# module.net
KiCad netlist of a schematic drawn in EAGLE
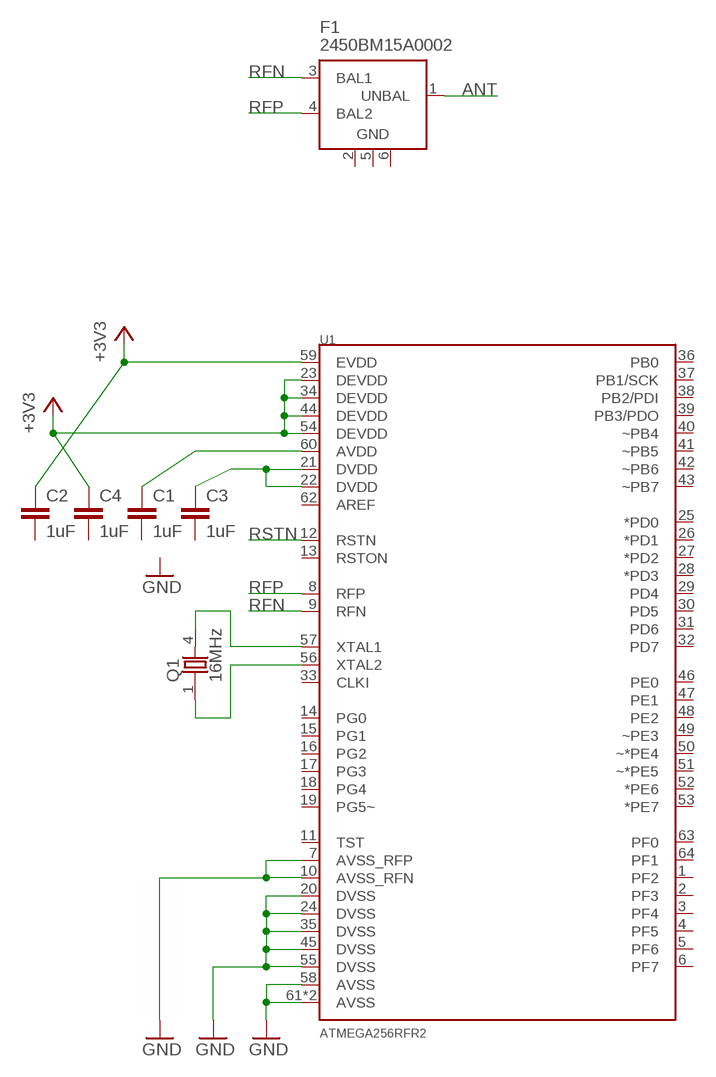
[diagram p0: schematic, sheet 1]

(export (version "E")
  (design (tool "Eeschema 10.0.6"))
  (components
    (comp (ref "C1")
      (value "1uF")
      (footprint "eagle-import:C0805K")
      (libsource (lib "eagle-import") (part "C-EUC0805K"))
    )
    (comp (ref "C2")
      (value "1uF")
      (footprint "eagle-import:C0805K")
      (libsource (lib "eagle-import") (part "C-EUC0805K"))
    )
    (comp (ref "C3")
      (value "1uF")
      (footprint "eagle-import:C0805K")
      (libsource (lib "eagle-import") (part "C-EUC0805K"))
    )
    (comp (ref "C4")
      (value "1uF")
      (footprint "eagle-import:C0805K")
      (libsource (lib "eagle-import") (part "C-EUC0805K"))
    )
    (comp (ref "F1")
      (value "2450BM15A0002")
      (footprint "eagle-import:2450BM15A0002")
      (libsource (lib "eagle-import") (part "2450BM15A0002"))
    )
    (comp (ref "Q1")
      (value "16MHz")
      (footprint "eagle-import:86SMX")
      (fields (field (name "MF") "C-MAC  FREQUENCY PRODUCTS LTD") (field (name "MPN") "XTAL003321- 86SMX"))
      (libsource (lib "eagle-import") (part "86SMX"))
    )
    (comp (ref "U1")
      (value "ATMEGA256RFR2")
      (footprint "eagle-import:QFN-64")
      (libsource (lib "eagle-import") (part "ATMEGA256RFR2"))
    )
  )
  (nets
    (net (code "1") (name "+3V3") (class "Default")
      (node (ref "C2") (pin "1") (pinfunction "1_1") (pintype "passive"))
      (node (ref "C4") (pin "1") (pinfunction "1_1") (pintype "passive"))
      (node (ref "U1") (pin "23") (pinfunction "DEVDD_23") (pintype "bidirectional"))
      (node (ref "U1") (pin "34") (pinfunction "DEVDD_34") (pintype "bidirectional"))
      (node (ref "U1") (pin "44") (pinfunction "DEVDD_44") (pintype "bidirectional"))
      (node (ref "U1") (pin "54") (pinfunction "DEVDD_54") (pintype "bidirectional"))
      (node (ref "U1") (pin "59") (pinfunction "EVDD_59") (pintype "bidirectional"))
    )
    (net (code "2") (name "/ANT") (class "Default")
      (node (ref "F1") (pin "1") (pinfunction "UNBAL_1") (pintype "passive"))
    )
    (net (code "3") (name "/RFN") (class "Default")
      (node (ref "F1") (pin "3") (pinfunction "BAL1_3") (pintype "passive"))
      (node (ref "U1") (pin "9") (pinfunction "RFN_9") (pintype "bidirectional"))
    )
    (net (code "4") (name "/RFP") (class "Default")
      (node (ref "F1") (pin "4") (pinfunction "BAL2_4") (pintype "passive"))
      (node (ref "U1") (pin "8") (pinfunction "RFP_8") (pintype "bidirectional"))
    )
    (net (code "5") (name "/RSTN") (class "Default")
      (node (ref "U1") (pin "12") (pinfunction "RSTN_12") (pintype "bidirectional"))
    )
    (net (code "6") (name "GND") (class "Default")
      (node (ref "U1") (pin "10") (pinfunction "AVSS_RFN_10") (pintype "bidirectional"))
      (node (ref "U1") (pin "20") (pinfunction "DVSS_20") (pintype "bidirectional"))
      (node (ref "U1") (pin "24") (pinfunction "DVSS_24") (pintype "bidirectional"))
      (node (ref "U1") (pin "35") (pinfunction "DVSS_35") (pintype "bidirectional"))
      (node (ref "U1") (pin "45") (pinfunction "DVSS_45") (pintype "bidirectional"))
      (node (ref "U1") (pin "55") (pinfunction "DVSS_55") (pintype "bidirectional"))
      (node (ref "U1") (pin "58") (pinfunction "AVSS_58") (pintype "bidirectional"))
      (node (ref "U1") (pin "61") (pinfunction "AVSS_61") (pintype "bidirectional"))
      (node (ref "U1") (pin "7") (pinfunction "AVSS_RFP_7") (pintype "bidirectional"))
      (node (ref "U1") (pin "PADDLE") (pinfunction "AVSS_PADDLE") (pintype "bidirectional"))
    )
    (net (code "7") (name "Net-(C3-Pad1)") (class "Default")
      (node (ref "C3") (pin "1") (pinfunction "1_1") (pintype "passive"))
      (node (ref "U1") (pin "21") (pinfunction "DVDD_21") (pintype "bidirectional"))
      (node (ref "U1") (pin "22") (pinfunction "DVDD_22") (pintype "bidirectional"))
    )
    (net (code "8") (name "Net-(Q1-2)") (class "Default")
      (node (ref "Q1") (pin "4") (pinfunction "2_4") (pintype "passive"))
      (node (ref "U1") (pin "57") (pinfunction "XTAL1_57") (pintype "bidirectional"))
    )
    (net (code "9") (name "Net-(U1-AVDD)") (class "Default")
      (node (ref "C1") (pin "1") (pinfunction "1_1") (pintype "passive"))
      (node (ref "U1") (pin "60") (pinfunction "AVDD_60") (pintype "bidirectional"))
    )
    (net (code "10") (name "Net-(U1-XTAL2)") (class "Default")
      (node (ref "Q1") (pin "1") (pinfunction "1_1") (pintype "passive"))
      (node (ref "U1") (pin "56") (pinfunction "XTAL2_56") (pintype "bidirectional"))
    )
    (net (code "11") (name "unconnected-(C1-Pad2)") (class "Default")
      (node (ref "C1") (pin "2") (pinfunction "2_2") (pintype "passive"))
    )
    (net (code "12") (name "unconnected-(C2-Pad2)") (class "Default")
      (node (ref "C2") (pin "2") (pinfunction "2_2") (pintype "passive"))
    )
    (net (code "13") (name "unconnected-(C3-Pad2)") (class "Default")
      (node (ref "C3") (pin "2") (pinfunction "2_2") (pintype "passive"))
    )
    (net (code "14") (name "unconnected-(C4-Pad2)") (class "Default")
      (node (ref "C4") (pin "2") (pinfunction "2_2") (pintype "passive"))
    )
    (net (code "15") (name "unconnected-(F1-GND-Pad2)") (class "Default")
      (node (ref "F1") (pin "2") (pinfunction "GND_2") (pintype "passive"))
    )
    (net (code "16") (name "unconnected-(F1-GND-Pad5)") (class "Default")
      (node (ref "F1") (pin "5") (pinfunction "GND_5") (pintype "passive"))
    )
    (net (code "17") (name "unconnected-(F1-GND-Pad6)") (class "Default")
      (node (ref "F1") (pin "6") (pinfunction "GND_6") (pintype "passive"))
    )
    (net (code "18") (name "unconnected-(U1-*PD0-Pad25)") (class "Default")
      (node (ref "U1") (pin "25") (pinfunction "*PD0_25") (pintype "bidirectional"))
    )
    (net (code "19") (name "unconnected-(U1-*PD1-Pad26)") (class "Default")
      (node (ref "U1") (pin "26") (pinfunction "*PD1_26") (pintype "bidirectional"))
    )
    (net (code "20") (name "unconnected-(U1-*PD2-Pad27)") (class "Default")
      (node (ref "U1") (pin "27") (pinfunction "*PD2_27") (pintype "bidirectional"))
    )
    (net (code "21") (name "unconnected-(U1-*PD3-Pad28)") (class "Default")
      (node (ref "U1") (pin "28") (pinfunction "*PD3_28") (pintype "bidirectional"))
    )
    (net (code "22") (name "unconnected-(U1-*PE6-Pad52)") (class "Default")
      (node (ref "U1") (pin "52") (pinfunction "*PE6_52") (pintype "bidirectional"))
    )
    (net (code "23") (name "unconnected-(U1-*PE7-Pad53)") (class "Default")
      (node (ref "U1") (pin "53") (pinfunction "*PE7_53") (pintype "bidirectional"))
    )
    (net (code "24") (name "unconnected-(U1-AREF-Pad62)") (class "Default")
      (node (ref "U1") (pin "62") (pinfunction "AREF_62") (pintype "bidirectional"))
    )
    (net (code "25") (name "unconnected-(U1-CLKI-Pad33)") (class "Default")
      (node (ref "U1") (pin "33") (pinfunction "CLKI_33") (pintype "bidirectional"))
    )
    (net (code "26") (name "unconnected-(U1-PB0-Pad36)") (class "Default")
      (node (ref "U1") (pin "36") (pinfunction "PB0_36") (pintype "bidirectional"))
    )
    (net (code "27") (name "unconnected-(U1-PB1{slash}SCK-Pad37)") (class "Default")
      (node (ref "U1") (pin "37") (pinfunction "PB1/SCK_37") (pintype "bidirectional"))
    )
    (net (code "28") (name "unconnected-(U1-PB2{slash}PDI-Pad38)") (class "Default")
      (node (ref "U1") (pin "38") (pinfunction "PB2/PDI_38") (pintype "bidirectional"))
    )
    (net (code "29") (name "unconnected-(U1-PB3{slash}PDO-Pad39)") (class "Default")
      (node (ref "U1") (pin "39") (pinfunction "PB3/PDO_39") (pintype "bidirectional"))
    )
    (net (code "30") (name "unconnected-(U1-PD4-Pad29)") (class "Default")
      (node (ref "U1") (pin "29") (pinfunction "PD4_29") (pintype "bidirectional"))
    )
    (net (code "31") (name "unconnected-(U1-PD5-Pad30)") (class "Default")
      (node (ref "U1") (pin "30") (pinfunction "PD5_30") (pintype "bidirectional"))
    )
    (net (code "32") (name "unconnected-(U1-PD6-Pad31)") (class "Default")
      (node (ref "U1") (pin "31") (pinfunction "PD6_31") (pintype "bidirectional"))
    )
    (net (code "33") (name "unconnected-(U1-PD7-Pad32)") (class "Default")
      (node (ref "U1") (pin "32") (pinfunction "PD7_32") (pintype "bidirectional"))
    )
    (net (code "34") (name "unconnected-(U1-PE0-Pad46)") (class "Default")
      (node (ref "U1") (pin "46") (pinfunction "PE0_46") (pintype "bidirectional"))
    )
    (net (code "35") (name "unconnected-(U1-PE1-Pad47)") (class "Default")
      (node (ref "U1") (pin "47") (pinfunction "PE1_47") (pintype "bidirectional"))
    )
    (net (code "36") (name "unconnected-(U1-PE2-Pad48)") (class "Default")
      (node (ref "U1") (pin "48") (pinfunction "PE2_48") (pintype "bidirectional"))
    )
    (net (code "37") (name "unconnected-(U1-PF0-Pad63)") (class "Default")
      (node (ref "U1") (pin "63") (pinfunction "PF0_63") (pintype "bidirectional"))
    )
    (net (code "38") (name "unconnected-(U1-PF1-Pad64)") (class "Default")
      (node (ref "U1") (pin "64") (pinfunction "PF1_64") (pintype "bidirectional"))
    )
    (net (code "39") (name "unconnected-(U1-PF2-Pad1)") (class "Default")
      (node (ref "U1") (pin "1") (pinfunction "PF2_1") (pintype "bidirectional"))
    )
    (net (code "40") (name "unconnected-(U1-PF3-Pad2)") (class "Default")
      (node (ref "U1") (pin "2") (pinfunction "PF3_2") (pintype "bidirectional"))
    )
    (net (code "41") (name "unconnected-(U1-PF4-Pad3)") (class "Default")
      (node (ref "U1") (pin "3") (pinfunction "PF4_3") (pintype "bidirectional"))
    )
    (net (code "42") (name "unconnected-(U1-PF5-Pad4)") (class "Default")
      (node (ref "U1") (pin "4") (pinfunction "PF5_4") (pintype "bidirectional"))
    )
    (net (code "43") (name "unconnected-(U1-PF6-Pad5)") (class "Default")
      (node (ref "U1") (pin "5") (pinfunction "PF6_5") (pintype "bidirectional"))
    )
    (net (code "44") (name "unconnected-(U1-PF7-Pad6)") (class "Default")
      (node (ref "U1") (pin "6") (pinfunction "PF7_6") (pintype "bidirectional"))
    )
    (net (code "45") (name "unconnected-(U1-PG0-Pad14)") (class "Default")
      (node (ref "U1") (pin "14") (pinfunction "PG0_14") (pintype "bidirectional"))
    )
    (net (code "46") (name "unconnected-(U1-PG1-Pad15)") (class "Default")
      (node (ref "U1") (pin "15") (pinfunction "PG1_15") (pintype "bidirectional"))
    )
    (net (code "47") (name "unconnected-(U1-PG2-Pad16)") (class "Default")
      (node (ref "U1") (pin "16") (pinfunction "PG2_16") (pintype "bidirectional"))
    )
    (net (code "48") (name "unconnected-(U1-PG3-Pad17)") (class "Default")
      (node (ref "U1") (pin "17") (pinfunction "PG3_17") (pintype "bidirectional"))
    )
    (net (code "49") (name "unconnected-(U1-PG4-Pad18)") (class "Default")
      (node (ref "U1") (pin "18") (pinfunction "PG4_18") (pintype "bidirectional"))
    )
    (net (code "50") (name "unconnected-(U1-PG5~{}-Pad19)") (class "Default")
      (node (ref "U1") (pin "19") (pinfunction "PG5~{}_19") (pintype "bidirectional"))
    )
    (net (code "51") (name "unconnected-(U1-RSTON-Pad13)") (class "Default")
      (node (ref "U1") (pin "13") (pinfunction "RSTON_13") (pintype "bidirectional"))
    )
    (net (code "52") (name "unconnected-(U1-TST-Pad11)") (class "Default")
      (node (ref "U1") (pin "11") (pinfunction "TST_11") (pintype "bidirectional"))
    )
    (net (code "53") (name "unconnected-(U1-~{*PE4}-Pad50)") (class "Default")
      (node (ref "U1") (pin "50") (pinfunction "~{*PE4}_50") (pintype "bidirectional"))
    )
    (net (code "54") (name "unconnected-(U1-~{*PE5}-Pad51)") (class "Default")
      (node (ref "U1") (pin "51") (pinfunction "~{*PE5}_51") (pintype "bidirectional"))
    )
    (net (code "55") (name "unconnected-(U1-~{PB4}-Pad40)") (class "Default")
      (node (ref "U1") (pin "40") (pinfunction "~{PB4}_40") (pintype "bidirectional"))
    )
    (net (code "56") (name "unconnected-(U1-~{PB5}-Pad41)") (class "Default")
      (node (ref "U1") (pin "41") (pinfunction "~{PB5}_41") (pintype "bidirectional"))
    )
    (net (code "57") (name "unconnected-(U1-~{PB6}-Pad42)") (class "Default")
      (node (ref "U1") (pin "42") (pinfunction "~{PB6}_42") (pintype "bidirectional"))
    )
    (net (code "58") (name "unconnected-(U1-~{PB7}-Pad43)") (class "Default")
      (node (ref "U1") (pin "43") (pinfunction "~{PB7}_43") (pintype "bidirectional"))
    )
    (net (code "59") (name "unconnected-(U1-~{PE3}-Pad49)") (class "Default")
      (node (ref "U1") (pin "49") (pinfunction "~{PE3}_49") (pintype "bidirectional"))
    )
  )
)
